# 4-20ma.net
KiCad netlist of a schematic drawn in EAGLE
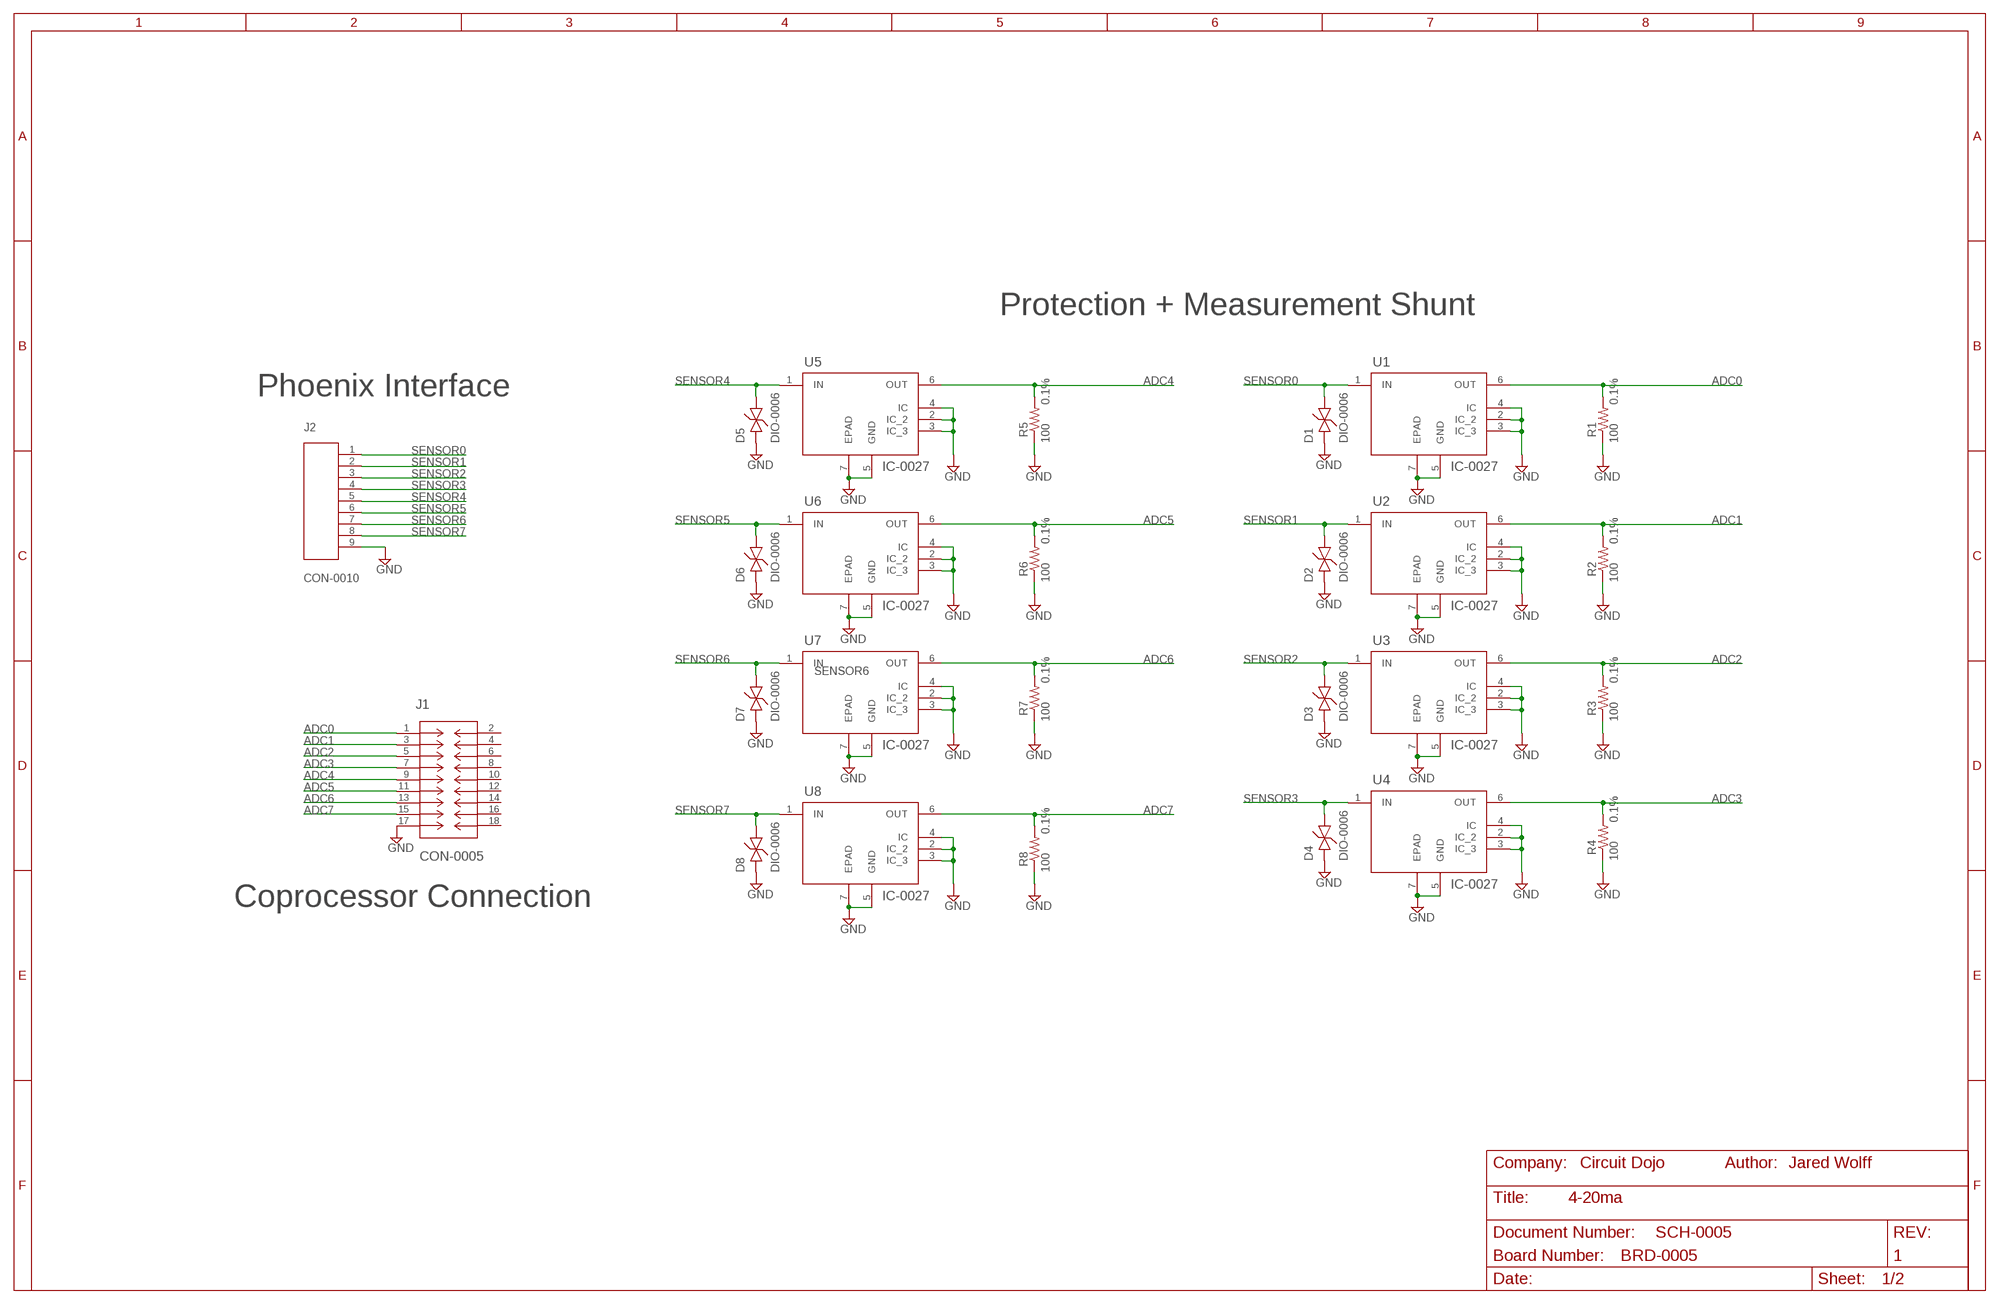
[diagram p0: schematic, sheet 1]
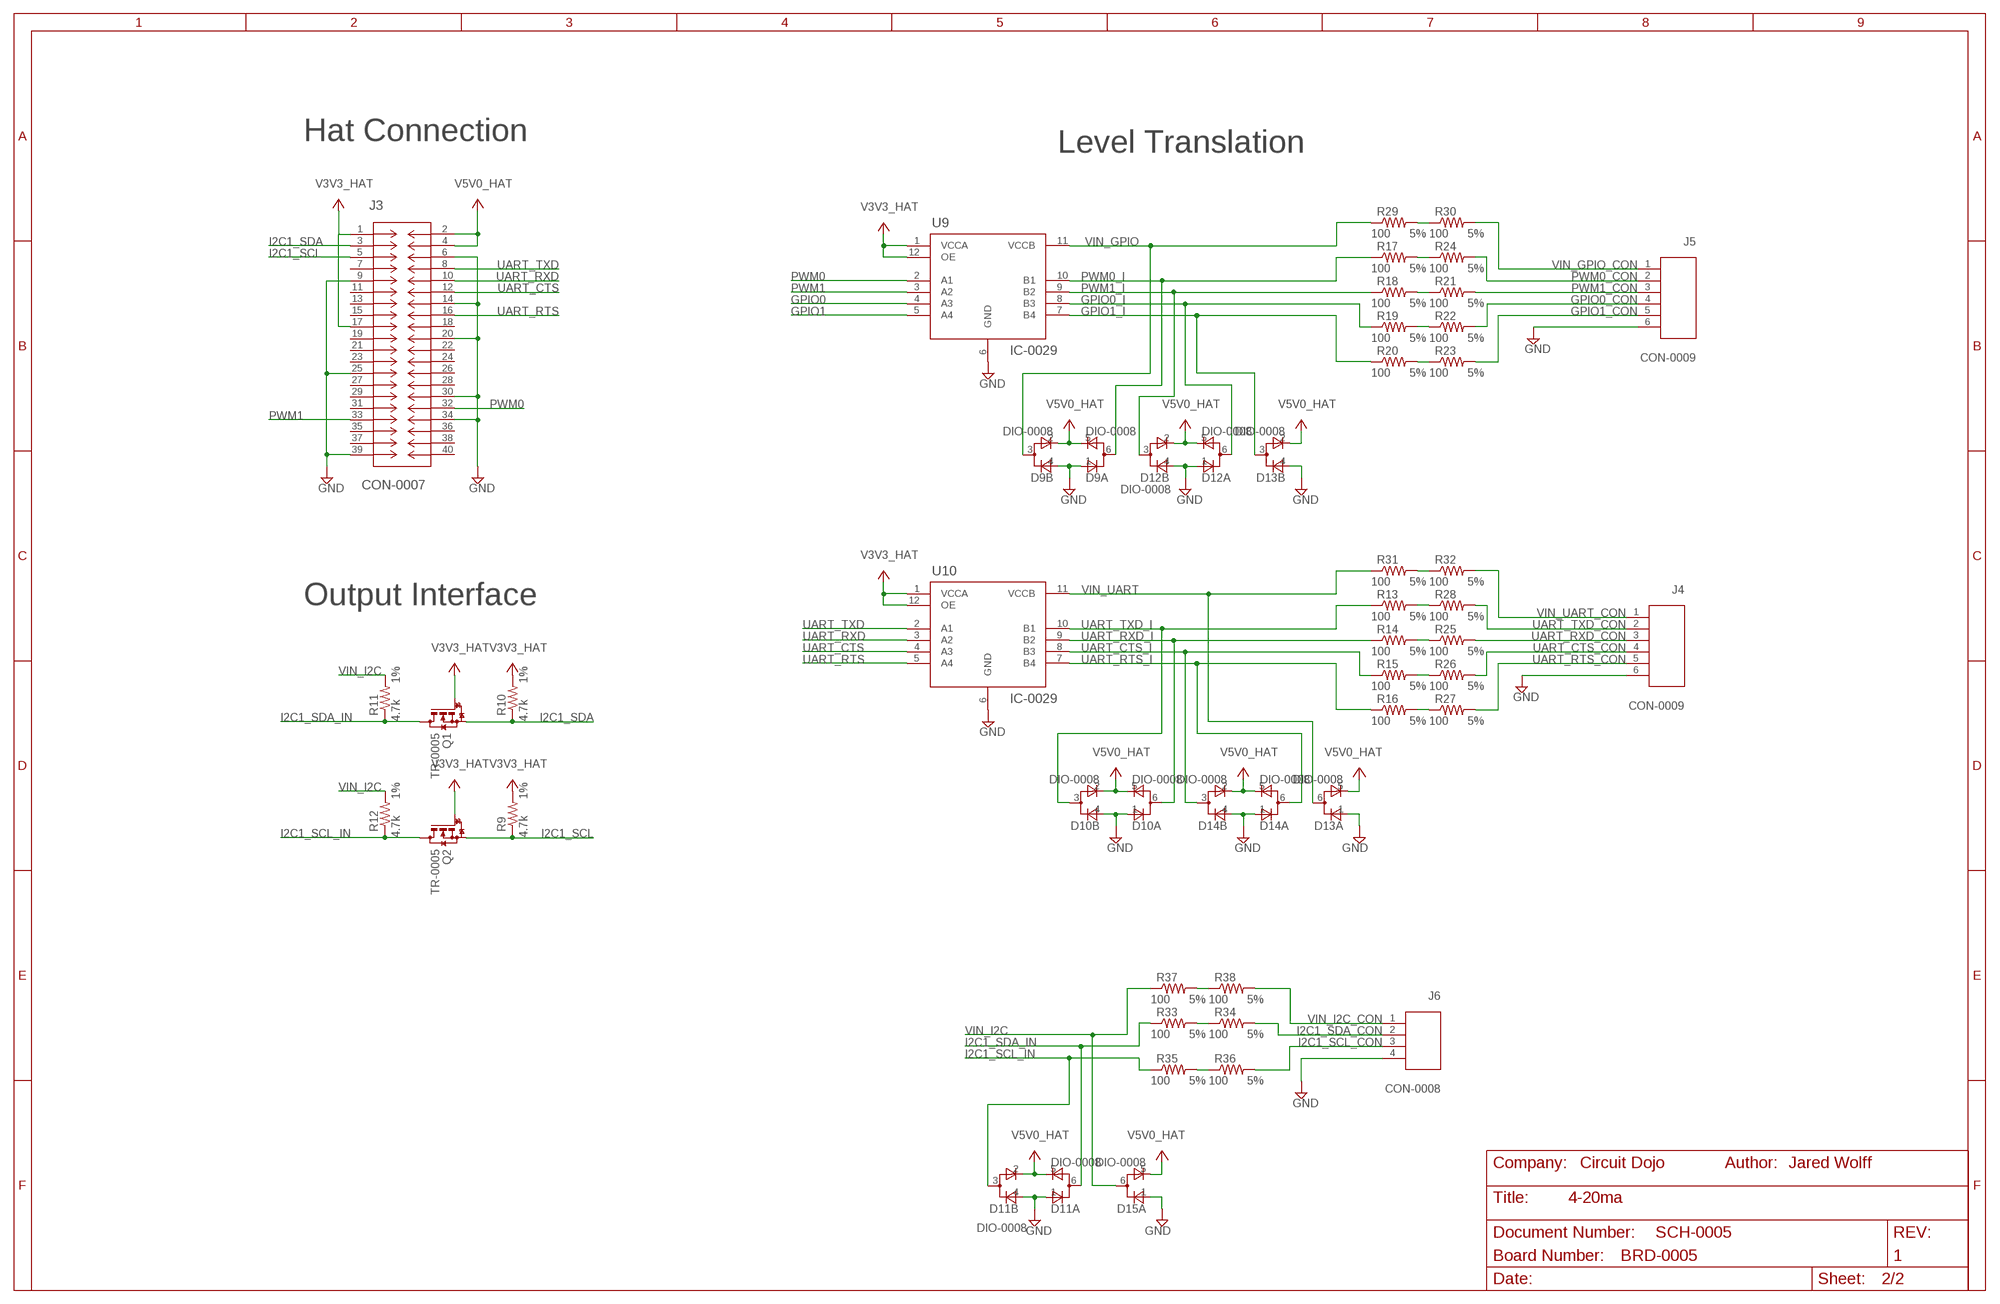
[diagram p1: schematic, sheet 2]

(export (version "E")
  (design (tool "Eeschema 10.0.6"))
  (components
    (comp (ref "D9")
      (value "DIO-0008")
      (footprint "eagle-import:SOT-563")
      (fields (field (name "MPN") "BAV99BRVA7"))
      (libsource (lib "eagle-import") (part "DIO-0008"))
    )
    (comp (ref "D10")
      (value "DIO-0008")
      (footprint "eagle-import:SOT-563")
      (fields (field (name "MPN") "BAV99BRVA7"))
      (libsource (lib "eagle-import") (part "DIO-0008"))
    )
    (comp (ref "D11")
      (value "DIO-0008")
      (footprint "eagle-import:SOT-563")
      (fields (field (name "MPN") "BAV99BRVA7"))
      (libsource (lib "eagle-import") (part "DIO-0008"))
    )
    (comp (ref "D12")
      (value "DIO-0008")
      (footprint "eagle-import:SOT-563")
      (fields (field (name "MPN") "BAV99BRVA7"))
      (libsource (lib "eagle-import") (part "DIO-0008"))
    )
    (comp (ref "D13")
      (value "DIO-0008")
      (footprint "eagle-import:SOT-563")
      (fields (field (name "MPN") "BAV99BRVA7"))
      (libsource (lib "eagle-import") (part "DIO-0008"))
    )
    (comp (ref "D14")
      (value "DIO-0008")
      (footprint "eagle-import:SOT-563")
      (fields (field (name "MPN") "BAV99BRVA7"))
      (libsource (lib "eagle-import") (part "DIO-0008"))
    )
    (comp (ref "D15")
      (value "DIO-0008")
      (footprint "eagle-import:SOT-563")
      (fields (field (name "MPN") "BAV99BRVA7"))
      (libsource (lib "eagle-import") (part "DIO-0008"))
    )
    (comp (ref "J3")
      (value "CON-0007")
      (footprint "eagle-import:CON40_2X20_TU_SSQ")
      (fields (field (name "MPN") "M20-7832042"))
      (libsource (lib "eagle-import") (part "CON-0007"))
    )
    (comp (ref "J4")
      (value "CON-0009")
      (footprint "eagle-import:CON-S6B-ZR")
      (fields (field (name "MPN") "S6B-ZR(LF)(SN)"))
      (libsource (lib "eagle-import") (part "CON-0009"))
    )
    (comp (ref "J5")
      (value "CON-0009")
      (footprint "eagle-import:CON-S6B-ZR")
      (fields (field (name "MPN") "S6B-ZR(LF)(SN)"))
      (libsource (lib "eagle-import") (part "CON-0009"))
    )
    (comp (ref "J6")
      (value "CON-0008")
      (footprint "eagle-import:CON-S4B-ZR")
      (fields (field (name "MPN") "S4B-ZR(LF)(SN)"))
      (libsource (lib "eagle-import") (part "CON-0008"))
    )
    (comp (ref "Q1")
      (value "TR-0005")
      (footprint "eagle-import:SOT323")
      (fields (field (name "MPN") "NX3020NAKW,115"))
      (libsource (lib "eagle-import") (part "TR-0005"))
    )
    (comp (ref "Q2")
      (value "TR-0005")
      (footprint "eagle-import:SOT323")
      (fields (field (name "MPN") "NX3020NAKW,115"))
      (libsource (lib "eagle-import") (part "TR-0005"))
    )
    (comp (ref "R9")
      (value "4.7k")
      (footprint "eagle-import:R0603")
      (fields (field (name "TOLERANCE") "1%") (field (name "MPN") "RMCF0603FT4K70"))
      (libsource (lib "eagle-import") (part "RES-0028"))
    )
    (comp (ref "R10")
      (value "4.7k")
      (footprint "eagle-import:R0603")
      (fields (field (name "TOLERANCE") "1%") (field (name "MPN") "RMCF0603FT4K70"))
      (libsource (lib "eagle-import") (part "RES-0028"))
    )
    (comp (ref "R11")
      (value "4.7k")
      (footprint "eagle-import:R0603")
      (fields (field (name "TOLERANCE") "1%") (field (name "MPN") "RMCF0603FT4K70"))
      (libsource (lib "eagle-import") (part "RES-0028"))
    )
    (comp (ref "R12")
      (value "4.7k")
      (footprint "eagle-import:R0603")
      (fields (field (name "TOLERANCE") "1%") (field (name "MPN") "RMCF0603FT4K70"))
      (libsource (lib "eagle-import") (part "RES-0028"))
    )
    (comp (ref "R13")
      (value "100")
      (footprint "eagle-import:R0603")
      (fields (field (name "TOLERANCE") "5%") (field (name "MPN") "ESR03EZPJ102"))
      (libsource (lib "eagle-import") (part "RES-0035"))
    )
    (comp (ref "R14")
      (value "100")
      (footprint "eagle-import:R0603")
      (fields (field (name "TOLERANCE") "5%") (field (name "MPN") "ESR03EZPJ102"))
      (libsource (lib "eagle-import") (part "RES-0035"))
    )
    (comp (ref "R15")
      (value "100")
      (footprint "eagle-import:R0603")
      (fields (field (name "TOLERANCE") "5%") (field (name "MPN") "ESR03EZPJ102"))
      (libsource (lib "eagle-import") (part "RES-0035"))
    )
    (comp (ref "R16")
      (value "100")
      (footprint "eagle-import:R0603")
      (fields (field (name "TOLERANCE") "5%") (field (name "MPN") "ESR03EZPJ102"))
      (libsource (lib "eagle-import") (part "RES-0035"))
    )
    (comp (ref "R17")
      (value "100")
      (footprint "eagle-import:R0603")
      (fields (field (name "TOLERANCE") "5%") (field (name "MPN") "ESR03EZPJ102"))
      (libsource (lib "eagle-import") (part "RES-0035"))
    )
    (comp (ref "R18")
      (value "100")
      (footprint "eagle-import:R0603")
      (fields (field (name "TOLERANCE") "5%") (field (name "MPN") "ESR03EZPJ102"))
      (libsource (lib "eagle-import") (part "RES-0035"))
    )
    (comp (ref "R19")
      (value "100")
      (footprint "eagle-import:R0603")
      (fields (field (name "TOLERANCE") "5%") (field (name "MPN") "ESR03EZPJ102"))
      (libsource (lib "eagle-import") (part "RES-0035"))
    )
    (comp (ref "R20")
      (value "100")
      (footprint "eagle-import:R0603")
      (fields (field (name "TOLERANCE") "5%") (field (name "MPN") "ESR03EZPJ102"))
      (libsource (lib "eagle-import") (part "RES-0035"))
    )
    (comp (ref "R21")
      (value "100")
      (footprint "eagle-import:R0603")
      (fields (field (name "TOLERANCE") "5%") (field (name "MPN") "ESR03EZPJ102"))
      (libsource (lib "eagle-import") (part "RES-0035"))
    )
    (comp (ref "R22")
      (value "100")
      (footprint "eagle-import:R0603")
      (fields (field (name "TOLERANCE") "5%") (field (name "MPN") "ESR03EZPJ102"))
      (libsource (lib "eagle-import") (part "RES-0035"))
    )
    (comp (ref "R23")
      (value "100")
      (footprint "eagle-import:R0603")
      (fields (field (name "TOLERANCE") "5%") (field (name "MPN") "ESR03EZPJ102"))
      (libsource (lib "eagle-import") (part "RES-0035"))
    )
    (comp (ref "R24")
      (value "100")
      (footprint "eagle-import:R0603")
      (fields (field (name "TOLERANCE") "5%") (field (name "MPN") "ESR03EZPJ102"))
      (libsource (lib "eagle-import") (part "RES-0035"))
    )
    (comp (ref "R25")
      (value "100")
      (footprint "eagle-import:R0603")
      (fields (field (name "TOLERANCE") "5%") (field (name "MPN") "ESR03EZPJ102"))
      (libsource (lib "eagle-import") (part "RES-0035"))
    )
    (comp (ref "R26")
      (value "100")
      (footprint "eagle-import:R0603")
      (fields (field (name "TOLERANCE") "5%") (field (name "MPN") "ESR03EZPJ102"))
      (libsource (lib "eagle-import") (part "RES-0035"))
    )
    (comp (ref "R27")
      (value "100")
      (footprint "eagle-import:R0603")
      (fields (field (name "TOLERANCE") "5%") (field (name "MPN") "ESR03EZPJ102"))
      (libsource (lib "eagle-import") (part "RES-0035"))
    )
    (comp (ref "R28")
      (value "100")
      (footprint "eagle-import:R0603")
      (fields (field (name "TOLERANCE") "5%") (field (name "MPN") "ESR03EZPJ102"))
      (libsource (lib "eagle-import") (part "RES-0035"))
    )
    (comp (ref "R29")
      (value "100")
      (footprint "eagle-import:R0603")
      (fields (field (name "TOLERANCE") "5%") (field (name "MPN") "ESR03EZPJ102"))
      (libsource (lib "eagle-import") (part "RES-0035"))
    )
    (comp (ref "R30")
      (value "100")
      (footprint "eagle-import:R0603")
      (fields (field (name "TOLERANCE") "5%") (field (name "MPN") "ESR03EZPJ102"))
      (libsource (lib "eagle-import") (part "RES-0035"))
    )
    (comp (ref "R31")
      (value "100")
      (footprint "eagle-import:R0603")
      (fields (field (name "TOLERANCE") "5%") (field (name "MPN") "ESR03EZPJ102"))
      (libsource (lib "eagle-import") (part "RES-0035"))
    )
    (comp (ref "R32")
      (value "100")
      (footprint "eagle-import:R0603")
      (fields (field (name "TOLERANCE") "5%") (field (name "MPN") "ESR03EZPJ102"))
      (libsource (lib "eagle-import") (part "RES-0035"))
    )
    (comp (ref "R33")
      (value "100")
      (footprint "eagle-import:R0603")
      (fields (field (name "TOLERANCE") "5%") (field (name "MPN") "ESR03EZPJ102"))
      (libsource (lib "eagle-import") (part "RES-0035"))
    )
    (comp (ref "R34")
      (value "100")
      (footprint "eagle-import:R0603")
      (fields (field (name "TOLERANCE") "5%") (field (name "MPN") "ESR03EZPJ102"))
      (libsource (lib "eagle-import") (part "RES-0035"))
    )
    (comp (ref "R35")
      (value "100")
      (footprint "eagle-import:R0603")
      (fields (field (name "TOLERANCE") "5%") (field (name "MPN") "ESR03EZPJ102"))
      (libsource (lib "eagle-import") (part "RES-0035"))
    )
    (comp (ref "R36")
      (value "100")
      (footprint "eagle-import:R0603")
      (fields (field (name "TOLERANCE") "5%") (field (name "MPN") "ESR03EZPJ102"))
      (libsource (lib "eagle-import") (part "RES-0035"))
    )
    (comp (ref "R37")
      (value "100")
      (footprint "eagle-import:R0603")
      (fields (field (name "TOLERANCE") "5%") (field (name "MPN") "ESR03EZPJ102"))
      (libsource (lib "eagle-import") (part "RES-0035"))
    )
    (comp (ref "R38")
      (value "100")
      (footprint "eagle-import:R0603")
      (fields (field (name "TOLERANCE") "5%") (field (name "MPN") "ESR03EZPJ102"))
      (libsource (lib "eagle-import") (part "RES-0035"))
    )
    (comp (ref "U9")
      (value "IC-0029")
      (footprint "eagle-import:RUT12")
      (fields (field (name "MPN") "TXB0104QRUTRQ1"))
      (libsource (lib "eagle-import") (part "IC-0029"))
    )
    (comp (ref "U10")
      (value "IC-0029")
      (footprint "eagle-import:RUT12")
      (fields (field (name "MPN") "TXB0104QRUTRQ1"))
      (libsource (lib "eagle-import") (part "IC-0029"))
    )
    (comp (ref "D1")
      (value "DIO-0006")
      (footprint "eagle-import:SMASERIES")
      (libsource (lib "eagle-import") (part "DIO-0006"))
    )
    (comp (ref "D2")
      (value "DIO-0006")
      (footprint "eagle-import:SMASERIES")
      (libsource (lib "eagle-import") (part "DIO-0006"))
    )
    (comp (ref "D3")
      (value "DIO-0006")
      (footprint "eagle-import:SMASERIES")
      (libsource (lib "eagle-import") (part "DIO-0006"))
    )
    (comp (ref "D4")
      (value "DIO-0006")
      (footprint "eagle-import:SMASERIES")
      (libsource (lib "eagle-import") (part "DIO-0006"))
    )
    (comp (ref "D5")
      (value "DIO-0006")
      (footprint "eagle-import:SMASERIES")
      (libsource (lib "eagle-import") (part "DIO-0006"))
    )
    (comp (ref "D6")
      (value "DIO-0006")
      (footprint "eagle-import:SMASERIES")
      (libsource (lib "eagle-import") (part "DIO-0006"))
    )
    (comp (ref "D7")
      (value "DIO-0006")
      (footprint "eagle-import:SMASERIES")
      (libsource (lib "eagle-import") (part "DIO-0006"))
    )
    (comp (ref "D8")
      (value "DIO-0006")
      (footprint "eagle-import:SMASERIES")
      (libsource (lib "eagle-import") (part "DIO-0006"))
    )
    (comp (ref "J1")
      (value "CON-0005")
      (footprint "eagle-import:CON18_2X9_TU_SSQ")
      (fields (field (name "MPN") "M20-7830942"))
      (libsource (lib "eagle-import") (part "CON-0005"))
    )
    (comp (ref "J2")
      (value "CON-0010")
      (footprint "eagle-import:CON-B9B-ZR")
      (fields (field (name "MPN") "B9B-ZR(LF)(SN)"))
      (libsource (lib "eagle-import") (part "CON-0010"))
    )
    (comp (ref "R1")
      (value "100")
      (footprint "eagle-import:R0603")
      (fields (field (name "TOLERANCE") "0.1%") (field (name "MPN") "ERA-3AEB101V"))
      (libsource (lib "eagle-import") (part "RES-0034"))
    )
    (comp (ref "R2")
      (value "100")
      (footprint "eagle-import:R0603")
      (fields (field (name "TOLERANCE") "0.1%") (field (name "MPN") "ERA-3AEB101V"))
      (libsource (lib "eagle-import") (part "RES-0034"))
    )
    (comp (ref "R3")
      (value "100")
      (footprint "eagle-import:R0603")
      (fields (field (name "TOLERANCE") "0.1%") (field (name "MPN") "ERA-3AEB101V"))
      (libsource (lib "eagle-import") (part "RES-0034"))
    )
    (comp (ref "R4")
      (value "100")
      (footprint "eagle-import:R0603")
      (fields (field (name "TOLERANCE") "0.1%") (field (name "MPN") "ERA-3AEB101V"))
      (libsource (lib "eagle-import") (part "RES-0034"))
    )
    (comp (ref "R5")
      (value "100")
      (footprint "eagle-import:R0603")
      (fields (field (name "TOLERANCE") "0.1%") (field (name "MPN") "ERA-3AEB101V"))
      (libsource (lib "eagle-import") (part "RES-0034"))
    )
    (comp (ref "R6")
      (value "100")
      (footprint "eagle-import:R0603")
      (fields (field (name "TOLERANCE") "0.1%") (field (name "MPN") "ERA-3AEB101V"))
      (libsource (lib "eagle-import") (part "RES-0034"))
    )
    (comp (ref "R7")
      (value "100")
      (footprint "eagle-import:R0603")
      (fields (field (name "TOLERANCE") "0.1%") (field (name "MPN") "ERA-3AEB101V"))
      (libsource (lib "eagle-import") (part "RES-0034"))
    )
    (comp (ref "R8")
      (value "100")
      (footprint "eagle-import:R0603")
      (fields (field (name "TOLERANCE") "0.1%") (field (name "MPN") "ERA-3AEB101V"))
      (libsource (lib "eagle-import") (part "RES-0034"))
    )
    (comp (ref "U1")
      (value "IC-0027")
      (footprint "eagle-import:21-0137I_T633-2")
      (fields (field (name "MPN") "MAX14626ETT+T"))
      (libsource (lib "eagle-import") (part "IC-0027"))
    )
    (comp (ref "U2")
      (value "IC-0027")
      (footprint "eagle-import:21-0137I_T633-2")
      (fields (field (name "MPN") "MAX14626ETT+T"))
      (libsource (lib "eagle-import") (part "IC-0027"))
    )
    (comp (ref "U3")
      (value "IC-0027")
      (footprint "eagle-import:21-0137I_T633-2")
      (fields (field (name "MPN") "MAX14626ETT+T"))
      (libsource (lib "eagle-import") (part "IC-0027"))
    )
    (comp (ref "U4")
      (value "IC-0027")
      (footprint "eagle-import:21-0137I_T633-2")
      (fields (field (name "MPN") "MAX14626ETT+T"))
      (libsource (lib "eagle-import") (part "IC-0027"))
    )
    (comp (ref "U5")
      (value "IC-0027")
      (footprint "eagle-import:21-0137I_T633-2")
      (fields (field (name "MPN") "MAX14626ETT+T"))
      (libsource (lib "eagle-import") (part "IC-0027"))
    )
    (comp (ref "U6")
      (value "IC-0027")
      (footprint "eagle-import:21-0137I_T633-2")
      (fields (field (name "MPN") "MAX14626ETT+T"))
      (libsource (lib "eagle-import") (part "IC-0027"))
    )
    (comp (ref "U7")
      (value "IC-0027")
      (footprint "eagle-import:21-0137I_T633-2")
      (fields (field (name "MPN") "MAX14626ETT+T"))
      (libsource (lib "eagle-import") (part "IC-0027"))
    )
    (comp (ref "U8")
      (value "IC-0027")
      (footprint "eagle-import:21-0137I_T633-2")
      (fields (field (name "MPN") "MAX14626ETT+T"))
      (libsource (lib "eagle-import") (part "IC-0027"))
    )
  )
  (nets
    (net (code "1") (name "ADC0") (class "Default")
      (node (ref "J1") (pin "1") (pinfunction "1_1") (pintype "passive"))
      (node (ref "R1") (pin "2") (pinfunction "2_2") (pintype "passive"))
      (node (ref "U1") (pin "6") (pinfunction "OUT_6") (pintype "output"))
    )
    (net (code "2") (name "ADC1") (class "Default")
      (node (ref "J1") (pin "3") (pinfunction "3_3") (pintype "passive"))
      (node (ref "R2") (pin "2") (pinfunction "2_2") (pintype "passive"))
      (node (ref "U2") (pin "6") (pinfunction "OUT_6") (pintype "output"))
    )
    (net (code "3") (name "ADC2") (class "Default")
      (node (ref "J1") (pin "5") (pinfunction "5_5") (pintype "passive"))
      (node (ref "R3") (pin "2") (pinfunction "2_2") (pintype "passive"))
      (node (ref "U3") (pin "6") (pinfunction "OUT_6") (pintype "output"))
    )
    (net (code "4") (name "ADC3") (class "Default")
      (node (ref "J1") (pin "7") (pinfunction "7_7") (pintype "passive"))
      (node (ref "R4") (pin "2") (pinfunction "2_2") (pintype "passive"))
      (node (ref "U4") (pin "6") (pinfunction "OUT_6") (pintype "output"))
    )
    (net (code "5") (name "ADC4") (class "Default")
      (node (ref "J1") (pin "9") (pinfunction "9_9") (pintype "passive"))
      (node (ref "R5") (pin "2") (pinfunction "2_2") (pintype "passive"))
      (node (ref "U5") (pin "6") (pinfunction "OUT_6") (pintype "output"))
    )
    (net (code "6") (name "ADC5") (class "Default")
      (node (ref "J1") (pin "11") (pinfunction "11_11") (pintype "passive"))
      (node (ref "R6") (pin "2") (pinfunction "2_2") (pintype "passive"))
      (node (ref "U6") (pin "6") (pinfunction "OUT_6") (pintype "output"))
    )
    (net (code "7") (name "ADC6") (class "Default")
      (node (ref "J1") (pin "13") (pinfunction "13_13") (pintype "passive"))
      (node (ref "R7") (pin "2") (pinfunction "2_2") (pintype "passive"))
      (node (ref "U7") (pin "6") (pinfunction "OUT_6") (pintype "output"))
    )
    (net (code "8") (name "ADC7") (class "Default")
      (node (ref "J1") (pin "15") (pinfunction "15_15") (pintype "passive"))
      (node (ref "R8") (pin "2") (pinfunction "2_2") (pintype "passive"))
      (node (ref "U8") (pin "6") (pinfunction "OUT_6") (pintype "output"))
    )
    (net (code "9") (name "GND") (class "Default")
      (node (ref "D1") (pin "1") (pinfunction "1_1") (pintype "bidirectional"))
      (node (ref "D10") (pin "1") (pinfunction "A_1") (pintype "passive"))
      (node (ref "D10") (pin "4") (pinfunction "A_4") (pintype "passive"))
      (node (ref "D11") (pin "1") (pinfunction "A_1") (pintype "passive"))
      (node (ref "D11") (pin "4") (pinfunction "A_4") (pintype "passive"))
      (node (ref "D12") (pin "1") (pinfunction "A_1") (pintype "passive"))
      (node (ref "D12") (pin "4") (pinfunction "A_4") (pintype "passive"))
      (node (ref "D13") (pin "1") (pinfunction "A_1") (pintype "passive"))
      (node (ref "D13") (pin "4") (pinfunction "A_4") (pintype "passive"))
      (node (ref "D14") (pin "1") (pinfunction "A_1") (pintype "passive"))
      (node (ref "D14") (pin "4") (pinfunction "A_4") (pintype "passive"))
      (node (ref "D15") (pin "1") (pinfunction "A_1") (pintype "passive"))
      (node (ref "D2") (pin "1") (pinfunction "1_1") (pintype "bidirectional"))
      (node (ref "D3") (pin "1") (pinfunction "1_1") (pintype "bidirectional"))
      (node (ref "D4") (pin "1") (pinfunction "1_1") (pintype "bidirectional"))
      (node (ref "D5") (pin "1") (pinfunction "1_1") (pintype "bidirectional"))
      (node (ref "D6") (pin "1") (pinfunction "1_1") (pintype "bidirectional"))
      (node (ref "D7") (pin "1") (pinfunction "1_1") (pintype "bidirectional"))
      (node (ref "D8") (pin "1") (pinfunction "1_1") (pintype "bidirectional"))
      (node (ref "D9") (pin "1") (pinfunction "A_1") (pintype "passive"))
      (node (ref "D9") (pin "4") (pinfunction "A_4") (pintype "passive"))
      (node (ref "J1") (pin "17") (pinfunction "17_17") (pintype "passive"))
      (node (ref "J2") (pin "9") (pinfunction "P$9_9") (pintype "bidirectional"))
      (node (ref "J3") (pin "14") (pinfunction "14_14") (pintype "passive"))
      (node (ref "J3") (pin "20") (pinfunction "20_20") (pintype "passive"))
      (node (ref "J3") (pin "25") (pinfunction "25_25") (pintype "passive"))
      (node (ref "J3") (pin "30") (pinfunction "30_30") (pintype "passive"))
      (node (ref "J3") (pin "34") (pinfunction "34_34") (pintype "passive"))
      (node (ref "J3") (pin "39") (pinfunction "39_39") (pintype "passive"))
      (node (ref "J3") (pin "6") (pinfunction "6_6") (pintype "passive"))
      (node (ref "J3") (pin "9") (pinfunction "9_9") (pintype "passive"))
      (node (ref "J4") (pin "6") (pinfunction "P$6_6") (pintype "bidirectional"))
      (node (ref "J5") (pin "6") (pinfunction "P$6_6") (pintype "bidirectional"))
      (node (ref "J6") (pin "4") (pinfunction "P$4_4") (pintype "bidirectional"))
      (node (ref "R1") (pin "1") (pinfunction "1_1") (pintype "passive"))
      (node (ref "R2") (pin "1") (pinfunction "1_1") (pintype "passive"))
      (node (ref "R3") (pin "1") (pinfunction "1_1") (pintype "passive"))
      (node (ref "R4") (pin "1") (pinfunction "1_1") (pintype "passive"))
      (node (ref "R5") (pin "1") (pinfunction "1_1") (pintype "passive"))
      (node (ref "R6") (pin "1") (pinfunction "1_1") (pintype "passive"))
      (node (ref "R7") (pin "1") (pinfunction "1_1") (pintype "passive"))
      (node (ref "R8") (pin "1") (pinfunction "1_1") (pintype "passive"))
      (node (ref "U1") (pin "2") (pinfunction "IC_2_2") (pintype "passive"))
      (node (ref "U1") (pin "3") (pinfunction "IC_3_3") (pintype "passive"))
      (node (ref "U1") (pin "4") (pinfunction "IC_4") (pintype "passive"))
      (node (ref "U1") (pin "5") (pinfunction "GND_5") (pintype "power_in"))
      (node (ref "U1") (pin "7") (pinfunction "EPAD_7") (pintype "passive"))
      (node (ref "U10") (pin "6") (pinfunction "GND_6") (pintype "power_in"))
      (node (ref "U2") (pin "2") (pinfunction "IC_2_2") (pintype "passive"))
      (node (ref "U2") (pin "3") (pinfunction "IC_3_3") (pintype "passive"))
      (node (ref "U2") (pin "4") (pinfunction "IC_4") (pintype "passive"))
      (node (ref "U2") (pin "5") (pinfunction "GND_5") (pintype "power_in"))
      (node (ref "U2") (pin "7") (pinfunction "EPAD_7") (pintype "passive"))
      (node (ref "U3") (pin "2") (pinfunction "IC_2_2") (pintype "passive"))
      (node (ref "U3") (pin "3") (pinfunction "IC_3_3") (pintype "passive"))
      (node (ref "U3") (pin "4") (pinfunction "IC_4") (pintype "passive"))
      (node (ref "U3") (pin "5") (pinfunction "GND_5") (pintype "power_in"))
      (node (ref "U3") (pin "7") (pinfunction "EPAD_7") (pintype "passive"))
      (node (ref "U4") (pin "2") (pinfunction "IC_2_2") (pintype "passive"))
      (node (ref "U4") (pin "3") (pinfunction "IC_3_3") (pintype "passive"))
      (node (ref "U4") (pin "4") (pinfunction "IC_4") (pintype "passive"))
      (node (ref "U4") (pin "5") (pinfunction "GND_5") (pintype "power_in"))
      (node (ref "U4") (pin "7") (pinfunction "EPAD_7") (pintype "passive"))
      (node (ref "U5") (pin "2") (pinfunction "IC_2_2") (pintype "passive"))
      (node (ref "U5") (pin "3") (pinfunction "IC_3_3") (pintype "passive"))
      (node (ref "U5") (pin "4") (pinfunction "IC_4") (pintype "passive"))
      (node (ref "U5") (pin "5") (pinfunction "GND_5") (pintype "power_in"))
      (node (ref "U5") (pin "7") (pinfunction "EPAD_7") (pintype "passive"))
      (node (ref "U6") (pin "2") (pinfunction "IC_2_2") (pintype "passive"))
      (node (ref "U6") (pin "3") (pinfunction "IC_3_3") (pintype "passive"))
      (node (ref "U6") (pin "4") (pinfunction "IC_4") (pintype "passive"))
      (node (ref "U6") (pin "5") (pinfunction "GND_5") (pintype "power_in"))
      (node (ref "U6") (pin "7") (pinfunction "EPAD_7") (pintype "passive"))
      (node (ref "U7") (pin "2") (pinfunction "IC_2_2") (pintype "passive"))
      (node (ref "U7") (pin "3") (pinfunction "IC_3_3") (pintype "passive"))
      (node (ref "U7") (pin "4") (pinfunction "IC_4") (pintype "passive"))
      (node (ref "U7") (pin "5") (pinfunction "GND_5") (pintype "power_in"))
      (node (ref "U7") (pin "7") (pinfunction "EPAD_7") (pintype "passive"))
      (node (ref "U8") (pin "2") (pinfunction "IC_2_2") (pintype "passive"))
      (node (ref "U8") (pin "3") (pinfunction "IC_3_3") (pintype "passive"))
      (node (ref "U8") (pin "4") (pinfunction "IC_4") (pintype "passive"))
      (node (ref "U8") (pin "5") (pinfunction "GND_5") (pintype "power_in"))
      (node (ref "U8") (pin "7") (pinfunction "EPAD_7") (pintype "passive"))
      (node (ref "U9") (pin "6") (pinfunction "GND_6") (pintype "power_in"))
    )
    (net (code "10") (name "GPIO0") (class "Default")
      (node (ref "U9") (pin "4") (pinfunction "A3_4") (pintype "bidirectional"))
    )
    (net (code "11") (name "GPIO0_CON") (class "Default")
      (node (ref "J5") (pin "4") (pinfunction "P$4_4") (pintype "bidirectional"))
      (node (ref "R22") (pin "2") (pinfunction "2_2") (pintype "passive"))
    )
    (net (code "12") (name "GPIO0_I") (class "Default")
      (node (ref "D12") (pin "6") (pinfunction "AC_6") (pintype "passive"))
      (node (ref "R19") (pin "1") (pinfunction "1_1") (pintype "passive"))
      (node (ref "U9") (pin "8") (pinfunction "B3_8") (pintype "bidirectional"))
    )
    (net (code "13") (name "GPIO1") (class "Default")
      (node (ref "U9") (pin "5") (pinfunction "A4_5") (pintype "bidirectional"))
    )
    (net (code "14") (name "GPIO1_CON") (class "Default")
      (node (ref "J5") (pin "5") (pinfunction "P$5_5") (pintype "bidirectional"))
      (node (ref "R23") (pin "2") (pinfunction "2_2") (pintype "passive"))
    )
    (net (code "15") (name "GPIO1_I") (class "Default")
      (node (ref "D13") (pin "3") (pinfunction "AC_3") (pintype "passive"))
      (node (ref "R20") (pin "1") (pinfunction "1_1") (pintype "passive"))
      (node (ref "U9") (pin "7") (pinfunction "B4_7") (pintype "bidirectional"))
    )
    (net (code "16") (name "I2C1_SCL") (class "Default")
      (node (ref "J3") (pin "5") (pinfunction "5_5") (pintype "passive"))
      (node (ref "Q2") (pin "S") (pinfunction "S_S") (pintype "passive"))
      (node (ref "R9") (pin "1") (pinfunction "1_1") (pintype "passive"))
    )
    (net (code "17") (name "I2C1_SCL_CON") (class "Default")
      (node (ref "J6") (pin "3") (pinfunction "P$3_3") (pintype "bidirectional"))
      (node (ref "R36") (pin "2") (pinfunction "2_2") (pintype "passive"))
    )
    (net (code "18") (name "I2C1_SCL_IN") (class "Default")
      (node (ref "D11") (pin "3") (pinfunction "AC_3") (pintype "passive"))
      (node (ref "Q2") (pin "D") (pinfunction "D_D") (pintype "passive"))
      (node (ref "R12") (pin "1") (pinfunction "1_1") (pintype "passive"))
      (node (ref "R35") (pin "1") (pinfunction "1_1") (pintype "passive"))
    )
    (net (code "19") (name "I2C1_SDA") (class "Default")
      (node (ref "J3") (pin "3") (pinfunction "3_3") (pintype "passive"))
      (node (ref "Q1") (pin "S") (pinfunction "S_S") (pintype "passive"))
      (node (ref "R10") (pin "1") (pinfunction "1_1") (pintype "passive"))
    )
    (net (code "20") (name "I2C1_SDA_CON") (class "Default")
      (node (ref "J6") (pin "2") (pinfunction "P$2_2") (pintype "bidirectional"))
      (node (ref "R34") (pin "2") (pinfunction "2_2") (pintype "passive"))
    )
    (net (code "21") (name "I2C1_SDA_IN") (class "Default")
      (node (ref "D11") (pin "6") (pinfunction "AC_6") (pintype "passive"))
      (node (ref "Q1") (pin "D") (pinfunction "D_D") (pintype "passive"))
      (node (ref "R11") (pin "1") (pinfunction "1_1") (pintype "passive"))
      (node (ref "R33") (pin "1") (pinfunction "1_1") (pintype "passive"))
    )
    (net (code "22") (name "Net-(R13-Pad2)") (class "Default")
      (node (ref "R13") (pin "2") (pinfunction "2_2") (pintype "passive"))
      (node (ref "R28") (pin "1") (pinfunction "1_1") (pintype "passive"))
    )
    (net (code "23") (name "Net-(R14-Pad2)") (class "Default")
      (node (ref "R14") (pin "2") (pinfunction "2_2") (pintype "passive"))
      (node (ref "R25") (pin "1") (pinfunction "1_1") (pintype "passive"))
    )
    (net (code "24") (name "Net-(R15-Pad2)") (class "Default")
      (node (ref "R15") (pin "2") (pinfunction "2_2") (pintype "passive"))
      (node (ref "R26") (pin "1") (pinfunction "1_1") (pintype "passive"))
    )
    (net (code "25") (name "Net-(R16-Pad2)") (class "Default")
      (node (ref "R16") (pin "2") (pinfunction "2_2") (pintype "passive"))
      (node (ref "R27") (pin "1") (pinfunction "1_1") (pintype "passive"))
    )
    (net (code "26") (name "Net-(R17-Pad2)") (class "Default")
      (node (ref "R17") (pin "2") (pinfunction "2_2") (pintype "passive"))
      (node (ref "R24") (pin "1") (pinfunction "1_1") (pintype "passive"))
    )
    (net (code "27") (name "Net-(R18-Pad2)") (class "Default")
      (node (ref "R18") (pin "2") (pinfunction "2_2") (pintype "passive"))
      (node (ref "R21") (pin "1") (pinfunction "1_1") (pintype "passive"))
    )
    (net (code "28") (name "Net-(R19-Pad2)") (class "Default")
      (node (ref "R19") (pin "2") (pinfunction "2_2") (pintype "passive"))
      (node (ref "R22") (pin "1") (pinfunction "1_1") (pintype "passive"))
    )
    (net (code "29") (name "Net-(R20-Pad2)") (class "Default")
      (node (ref "R20") (pin "2") (pinfunction "2_2") (pintype "passive"))
      (node (ref "R23") (pin "1") (pinfunction "1_1") (pintype "passive"))
    )
    (net (code "30") (name "Net-(R29-Pad2)") (class "Default")
      (node (ref "R29") (pin "2") (pinfunction "2_2") (pintype "passive"))
      (node (ref "R30") (pin "1") (pinfunction "1_1") (pintype "passive"))
    )
    (net (code "31") (name "Net-(R31-Pad2)") (class "Default")
      (node (ref "R31") (pin "2") (pinfunction "2_2") (pintype "passive"))
      (node (ref "R32") (pin "1") (pinfunction "1_1") (pintype "passive"))
    )
    (net (code "32") (name "Net-(R33-Pad2)") (class "Default")
      (node (ref "R33") (pin "2") (pinfunction "2_2") (pintype "passive"))
      (node (ref "R34") (pin "1") (pinfunction "1_1") (pintype "passive"))
    )
    (net (code "33") (name "Net-(R35-Pad2)") (class "Default")
      (node (ref "R35") (pin "2") (pinfunction "2_2") (pintype "passive"))
      (node (ref "R36") (pin "1") (pinfunction "1_1") (pintype "passive"))
    )
    (net (code "34") (name "Net-(R37-Pad2)") (class "Default")
      (node (ref "R37") (pin "2") (pinfunction "2_2") (pintype "passive"))
      (node (ref "R38") (pin "1") (pinfunction "1_1") (pintype "passive"))
    )
    (net (code "35") (name "PWM0") (class "Default")
      (node (ref "J3") (pin "32") (pinfunction "32_32") (pintype "passive"))
      (node (ref "U9") (pin "2") (pinfunction "A1_2") (pintype "bidirectional"))
    )
    (net (code "36") (name "PWM0_CON") (class "Default")
      (node (ref "J5") (pin "2") (pinfunction "P$2_2") (pintype "bidirectional"))
      (node (ref "R24") (pin "2") (pinfunction "2_2") (pintype "passive"))
    )
    (net (code "37") (name "PWM0_I") (class "Default")
      (node (ref "D9") (pin "6") (pinfunction "AC_6") (pintype "passive"))
      (node (ref "R17") (pin "1") (pinfunction "1_1") (pintype "passive"))
      (node (ref "U9") (pin "10") (pinfunction "B1_10") (pintype "bidirectional"))
    )
    (net (code "38") (name "PWM1") (class "Default")
      (node (ref "J3") (pin "33") (pinfunction "33_33") (pintype "passive"))
      (node (ref "U9") (pin "3") (pinfunction "A2_3") (pintype "bidirectional"))
    )
    (net (code "39") (name "PWM1_CON") (class "Default")
      (node (ref "J5") (pin "3") (pinfunction "P$3_3") (pintype "bidirectional"))
      (node (ref "R21") (pin "2") (pinfunction "2_2") (pintype "passive"))
    )
    (net (code "40") (name "PWM1_I") (class "Default")
      (node (ref "D12") (pin "3") (pinfunction "AC_3") (pintype "passive"))
      (node (ref "R18") (pin "1") (pinfunction "1_1") (pintype "passive"))
      (node (ref "U9") (pin "9") (pinfunction "B2_9") (pintype "bidirectional"))
    )
    (net (code "41") (name "SENSOR0") (class "Default")
      (node (ref "D1") (pin "2") (pinfunction "2_2") (pintype "bidirectional"))
      (node (ref "J2") (pin "1") (pinfunction "P$1_1") (pintype "bidirectional"))
      (node (ref "U1") (pin "1") (pinfunction "IN_1") (pintype "input"))
    )
    (net (code "42") (name "SENSOR1") (class "Default")
      (node (ref "D2") (pin "2") (pinfunction "2_2") (pintype "bidirectional"))
      (node (ref "J2") (pin "2") (pinfunction "P$2_2") (pintype "bidirectional"))
      (node (ref "U2") (pin "1") (pinfunction "IN_1") (pintype "input"))
    )
    (net (code "43") (name "SENSOR2") (class "Default")
      (node (ref "D3") (pin "2") (pinfunction "2_2") (pintype "bidirectional"))
      (node (ref "J2") (pin "3") (pinfunction "P$3_3") (pintype "bidirectional"))
      (node (ref "U3") (pin "1") (pinfunction "IN_1") (pintype "input"))
    )
    (net (code "44") (name "SENSOR3") (class "Default")
      (node (ref "D4") (pin "2") (pinfunction "2_2") (pintype "bidirectional"))
      (node (ref "J2") (pin "4") (pinfunction "P$4_4") (pintype "bidirectional"))
      (node (ref "U4") (pin "1") (pinfunction "IN_1") (pintype "input"))
    )
    (net (code "45") (name "SENSOR4") (class "Default")
      (node (ref "D5") (pin "2") (pinfunction "2_2") (pintype "bidirectional"))
      (node (ref "J2") (pin "5") (pinfunction "P$5_5") (pintype "bidirectional"))
      (node (ref "U5") (pin "1") (pinfunction "IN_1") (pintype "input"))
    )
    (net (code "46") (name "SENSOR5") (class "Default")
      (node (ref "D6") (pin "2") (pinfunction "2_2") (pintype "bidirectional"))
      (node (ref "J2") (pin "6") (pinfunction "P$6_6") (pintype "bidirectional"))
      (node (ref "U6") (pin "1") (pinfunction "IN_1") (pintype "input"))
    )
    (net (code "47") (name "SENSOR6") (class "Default")
      (node (ref "D7") (pin "2") (pinfunction "2_2") (pintype "bidirectional"))
      (node (ref "J2") (pin "7") (pinfunction "P$7_7") (pintype "bidirectional"))
      (node (ref "U7") (pin "1") (pinfunction "IN_1") (pintype "input"))
    )
    (net (code "48") (name "SENSOR7") (class "Default")
      (node (ref "D8") (pin "2") (pinfunction "2_2") (pintype "bidirectional"))
      (node (ref "J2") (pin "8") (pinfunction "P$8_8") (pintype "bidirectional"))
      (node (ref "U8") (pin "1") (pinfunction "IN_1") (pintype "input"))
    )
    (net (code "49") (name "UART_CTS") (class "Default")
      (node (ref "J3") (pin "12") (pinfunction "12_12") (pintype "passive"))
      (node (ref "U10") (pin "4") (pinfunction "A3_4") (pintype "bidirectional"))
    )
    (net (code "50") (name "UART_CTS_CON") (class "Default")
      (node (ref "J4") (pin "4") (pinfunction "P$4_4") (pintype "bidirectional"))
      (node (ref "R26") (pin "2") (pinfunction "2_2") (pintype "passive"))
    )
    (net (code "51") (name "UART_CTS_I") (class "Default")
      (node (ref "D14") (pin "3") (pinfunction "AC_3") (pintype "passive"))
      (node (ref "R15") (pin "1") (pinfunction "1_1") (pintype "passive"))
      (node (ref "U10") (pin "8") (pinfunction "B3_8") (pintype "bidirectional"))
    )
    (net (code "52") (name "UART_RTS") (class "Default")
      (node (ref "J3") (pin "16") (pinfunction "16_16") (pintype "passive"))
      (node (ref "U10") (pin "5") (pinfunction "A4_5") (pintype "bidirectional"))
    )
    (net (code "53") (name "UART_RTS_CON") (class "Default")
      (node (ref "J4") (pin "5") (pinfunction "P$5_5") (pintype "bidirectional"))
      (node (ref "R27") (pin "2") (pinfunction "2_2") (pintype "passive"))
    )
    (net (code "54") (name "UART_RTS_I") (class "Default")
      (node (ref "D14") (pin "6") (pinfunction "AC_6") (pintype "passive"))
      (node (ref "R16") (pin "1") (pinfunction "1_1") (pintype "passive"))
      (node (ref "U10") (pin "7") (pinfunction "B4_7") (pintype "bidirectional"))
    )
    (net (code "55") (name "UART_RXD") (class "Default")
      (node (ref "J3") (pin "10") (pinfunction "10_10") (pintype "passive"))
      (node (ref "U10") (pin "3") (pinfunction "A2_3") (pintype "bidirectional"))
    )
    (net (code "56") (name "UART_RXD_CON") (class "Default")
      (node (ref "J4") (pin "3") (pinfunction "P$3_3") (pintype "bidirectional"))
      (node (ref "R25") (pin "2") (pinfunction "2_2") (pintype "passive"))
    )
    (net (code "57") (name "UART_RXD_I") (class "Default")
      (node (ref "D10") (pin "6") (pinfunction "AC_6") (pintype "passive"))
      (node (ref "R14") (pin "1") (pinfunction "1_1") (pintype "passive"))
      (node (ref "U10") (pin "9") (pinfunction "B2_9") (pintype "bidirectional"))
    )
    (net (code "58") (name "UART_TXD") (class "Default")
      (node (ref "J3") (pin "8") (pinfunction "8_8") (pintype "passive"))
      (node (ref "U10") (pin "2") (pinfunction "A1_2") (pintype "bidirectional"))
    )
    (net (code "59") (name "UART_TXD_CON") (class "Default")
      (node (ref "J4") (pin "2") (pinfunction "P$2_2") (pintype "bidirectional"))
      (node (ref "R28") (pin "2") (pinfunction "2_2") (pintype "passive"))
    )
    (net (code "60") (name "UART_TXD_I") (class "Default")
      (node (ref "D10") (pin "3") (pinfunction "AC_3") (pintype "passive"))
      (node (ref "R13") (pin "1") (pinfunction "1_1") (pintype "passive"))
      (node (ref "U10") (pin "10") (pinfunction "B1_10") (pintype "bidirectional"))
    )
    (net (code "61") (name "V3V3_HAT") (class "Default")
      (node (ref "J3") (pin "1") (pinfunction "1_1") (pintype "passive"))
      (node (ref "J3") (pin "17") (pinfunction "17_17") (pintype "passive"))
      (node (ref "Q1") (pin "G") (pinfunction "G_G") (pintype "passive"))
      (node (ref "Q2") (pin "G") (pinfunction "G_G") (pintype "passive"))
      (node (ref "R10") (pin "2") (pinfunction "2_2") (pintype "passive"))
      (node (ref "R9") (pin "2") (pinfunction "2_2") (pintype "passive"))
      (node (ref "U10") (pin "1") (pinfunction "VCCA_1") (pintype "power_in"))
      (node (ref "U10") (pin "12") (pinfunction "OE_12") (pintype "input"))
      (node (ref "U9") (pin "1") (pinfunction "VCCA_1") (pintype "power_in"))
      (node (ref "U9") (pin "12") (pinfunction "OE_12") (pintype "input"))
    )
    (net (code "62") (name "V5V0_HAT") (class "Default")
      (node (ref "D10") (pin "2") (pinfunction "C_2") (pintype "passive"))
      (node (ref "D10") (pin "5") (pinfunction "C_5") (pintype "passive"))
      (node (ref "D11") (pin "2") (pinfunction "C_2") (pintype "passive"))
      (node (ref "D11") (pin "5") (pinfunction "C_5") (pintype "passive"))
      (node (ref "D12") (pin "2") (pinfunction "C_2") (pintype "passive"))
      (node (ref "D12") (pin "5") (pinfunction "C_5") (pintype "passive"))
      (node (ref "D13") (pin "2") (pinfunction "C_2") (pintype "passive"))
      (node (ref "D13") (pin "5") (pinfunction "C_5") (pintype "passive"))
      (node (ref "D14") (pin "2") (pinfunction "C_2") (pintype "passive"))
      (node (ref "D14") (pin "5") (pinfunction "C_5") (pintype "passive"))
      (node (ref "D15") (pin "5") (pinfunction "C_5") (pintype "passive"))
      (node (ref "D9") (pin "2") (pinfunction "C_2") (pintype "passive"))
      (node (ref "D9") (pin "5") (pinfunction "C_5") (pintype "passive"))
      (node (ref "J3") (pin "2") (pinfunction "2_2") (pintype "passive"))
      (node (ref "J3") (pin "4") (pinfunction "4_4") (pintype "passive"))
    )
    (net (code "63") (name "VIN_GPIO") (class "Default")
      (node (ref "D9") (pin "3") (pinfunction "AC_3") (pintype "passive"))
      (node (ref "R29") (pin "1") (pinfunction "1_1") (pintype "passive"))
      (node (ref "U9") (pin "11") (pinfunction "VCCB_11") (pintype "power_in"))
    )
    (net (code "64") (name "VIN_GPIO_CON") (class "Default")
      (node (ref "J5") (pin "1") (pinfunction "P$1_1") (pintype "bidirectional"))
      (node (ref "R30") (pin "2") (pinfunction "2_2") (pintype "passive"))
    )
    (net (code "65") (name "VIN_I2C") (class "Default")
      (node (ref "D15") (pin "6") (pinfunction "AC_6") (pintype "passive"))
      (node (ref "R11") (pin "2") (pinfunction "2_2") (pintype "passive"))
      (node (ref "R12") (pin "2") (pinfunction "2_2") (pintype "passive"))
      (node (ref "R37") (pin "1") (pinfunction "1_1") (pintype "passive"))
    )
    (net (code "66") (name "VIN_I2C_CON") (class "Default")
      (node (ref "J6") (pin "1") (pinfunction "P$1_1") (pintype "bidirectional"))
      (node (ref "R38") (pin "2") (pinfunction "2_2") (pintype "passive"))
    )
    (net (code "67") (name "VIN_UART") (class "Default")
      (node (ref "D13") (pin "6") (pinfunction "AC_6") (pintype "passive"))
      (node (ref "R31") (pin "1") (pinfunction "1_1") (pintype "passive"))
      (node (ref "U10") (pin "11") (pinfunction "VCCB_11") (pintype "power_in"))
    )
    (net (code "68") (name "VIN_UART_CON") (class "Default")
      (node (ref "J4") (pin "1") (pinfunction "P$1_1") (pintype "bidirectional"))
      (node (ref "R32") (pin "2") (pinfunction "2_2") (pintype "passive"))
    )
    (net (code "69") (name "unconnected-(J1-Pad2)") (class "Default")
      (node (ref "J1") (pin "2") (pinfunction "2_2") (pintype "passive"))
    )
    (net (code "70") (name "unconnected-(J1-Pad4)") (class "Default")
      (node (ref "J1") (pin "4") (pinfunction "4_4") (pintype "passive"))
    )
    (net (code "71") (name "unconnected-(J1-Pad6)") (class "Default")
      (node (ref "J1") (pin "6") (pinfunction "6_6") (pintype "passive"))
    )
    (net (code "72") (name "unconnected-(J1-Pad8)") (class "Default")
      (node (ref "J1") (pin "8") (pinfunction "8_8") (pintype "passive"))
    )
    (net (code "73") (name "unconnected-(J1-Pad10)") (class "Default")
      (node (ref "J1") (pin "10") (pinfunction "10_10") (pintype "passive"))
    )
    (net (code "74") (name "unconnected-(J1-Pad12)") (class "Default")
      (node (ref "J1") (pin "12") (pinfunction "12_12") (pintype "passive"))
    )
    (net (code "75") (name "unconnected-(J1-Pad14)") (class "Default")
      (node (ref "J1") (pin "14") (pinfunction "14_14") (pintype "passive"))
    )
    (net (code "76") (name "unconnected-(J1-Pad16)") (class "Default")
      (node (ref "J1") (pin "16") (pinfunction "16_16") (pintype "passive"))
    )
    (net (code "77") (name "unconnected-(J1-Pad18)") (class "Default")
      (node (ref "J1") (pin "18") (pinfunction "18_18") (pintype "passive"))
    )
    (net (code "78") (name "unconnected-(J3-Pad7)") (class "Default")
      (node (ref "J3") (pin "7") (pinfunction "7_7") (pintype "passive"))
    )
    (net (code "79") (name "unconnected-(J3-Pad11)") (class "Default")
      (node (ref "J3") (pin "11") (pinfunction "11_11") (pintype "passive"))
    )
    (net (code "80") (name "unconnected-(J3-Pad13)") (class "Default")
      (node (ref "J3") (pin "13") (pinfunction "13_13") (pintype "passive"))
    )
    (net (code "81") (name "unconnected-(J3-Pad15)") (class "Default")
      (node (ref "J3") (pin "15") (pinfunction "15_15") (pintype "passive"))
    )
    (net (code "82") (name "unconnected-(J3-Pad18)") (class "Default")
      (node (ref "J3") (pin "18") (pinfunction "18_18") (pintype "passive"))
    )
    (net (code "83") (name "unconnected-(J3-Pad19)") (class "Default")
      (node (ref "J3") (pin "19") (pinfunction "19_19") (pintype "passive"))
    )
    (net (code "84") (name "unconnected-(J3-Pad21)") (class "Default")
      (node (ref "J3") (pin "21") (pinfunction "21_21") (pintype "passive"))
    )
    (net (code "85") (name "unconnected-(J3-Pad22)") (class "Default")
      (node (ref "J3") (pin "22") (pinfunction "22_22") (pintype "passive"))
    )
    (net (code "86") (name "unconnected-(J3-Pad23)") (class "Default")
      (node (ref "J3") (pin "23") (pinfunction "23_23") (pintype "passive"))
    )
    (net (code "87") (name "unconnected-(J3-Pad24)") (class "Default")
      (node (ref "J3") (pin "24") (pinfunction "24_24") (pintype "passive"))
    )
    (net (code "88") (name "unconnected-(J3-Pad26)") (class "Default")
      (node (ref "J3") (pin "26") (pinfunction "26_26") (pintype "passive"))
    )
    (net (code "89") (name "unconnected-(J3-Pad27)") (class "Default")
      (node (ref "J3") (pin "27") (pinfunction "27_27") (pintype "passive"))
    )
    (net (code "90") (name "unconnected-(J3-Pad28)") (class "Default")
      (node (ref "J3") (pin "28") (pinfunction "28_28") (pintype "passive"))
    )
    (net (code "91") (name "unconnected-(J3-Pad29)") (class "Default")
      (node (ref "J3") (pin "29") (pinfunction "29_29") (pintype "passive"))
    )
    (net (code "92") (name "unconnected-(J3-Pad31)") (class "Default")
      (node (ref "J3") (pin "31") (pinfunction "31_31") (pintype "passive"))
    )
    (net (code "93") (name "unconnected-(J3-Pad35)") (class "Default")
      (node (ref "J3") (pin "35") (pinfunction "35_35") (pintype "passive"))
    )
    (net (code "94") (name "unconnected-(J3-Pad36)") (class "Default")
      (node (ref "J3") (pin "36") (pinfunction "36_36") (pintype "passive"))
    )
    (net (code "95") (name "unconnected-(J3-Pad37)") (class "Default")
      (node (ref "J3") (pin "37") (pinfunction "37_37") (pintype "passive"))
    )
    (net (code "96") (name "unconnected-(J3-Pad38)") (class "Default")
      (node (ref "J3") (pin "38") (pinfunction "38_38") (pintype "passive"))
    )
    (net (code "97") (name "unconnected-(J3-Pad40)") (class "Default")
      (node (ref "J3") (pin "40") (pinfunction "40_40") (pintype "passive"))
    )
  )
)
